# schematics.net
KiCad netlist of a schematic drawn in EAGLE
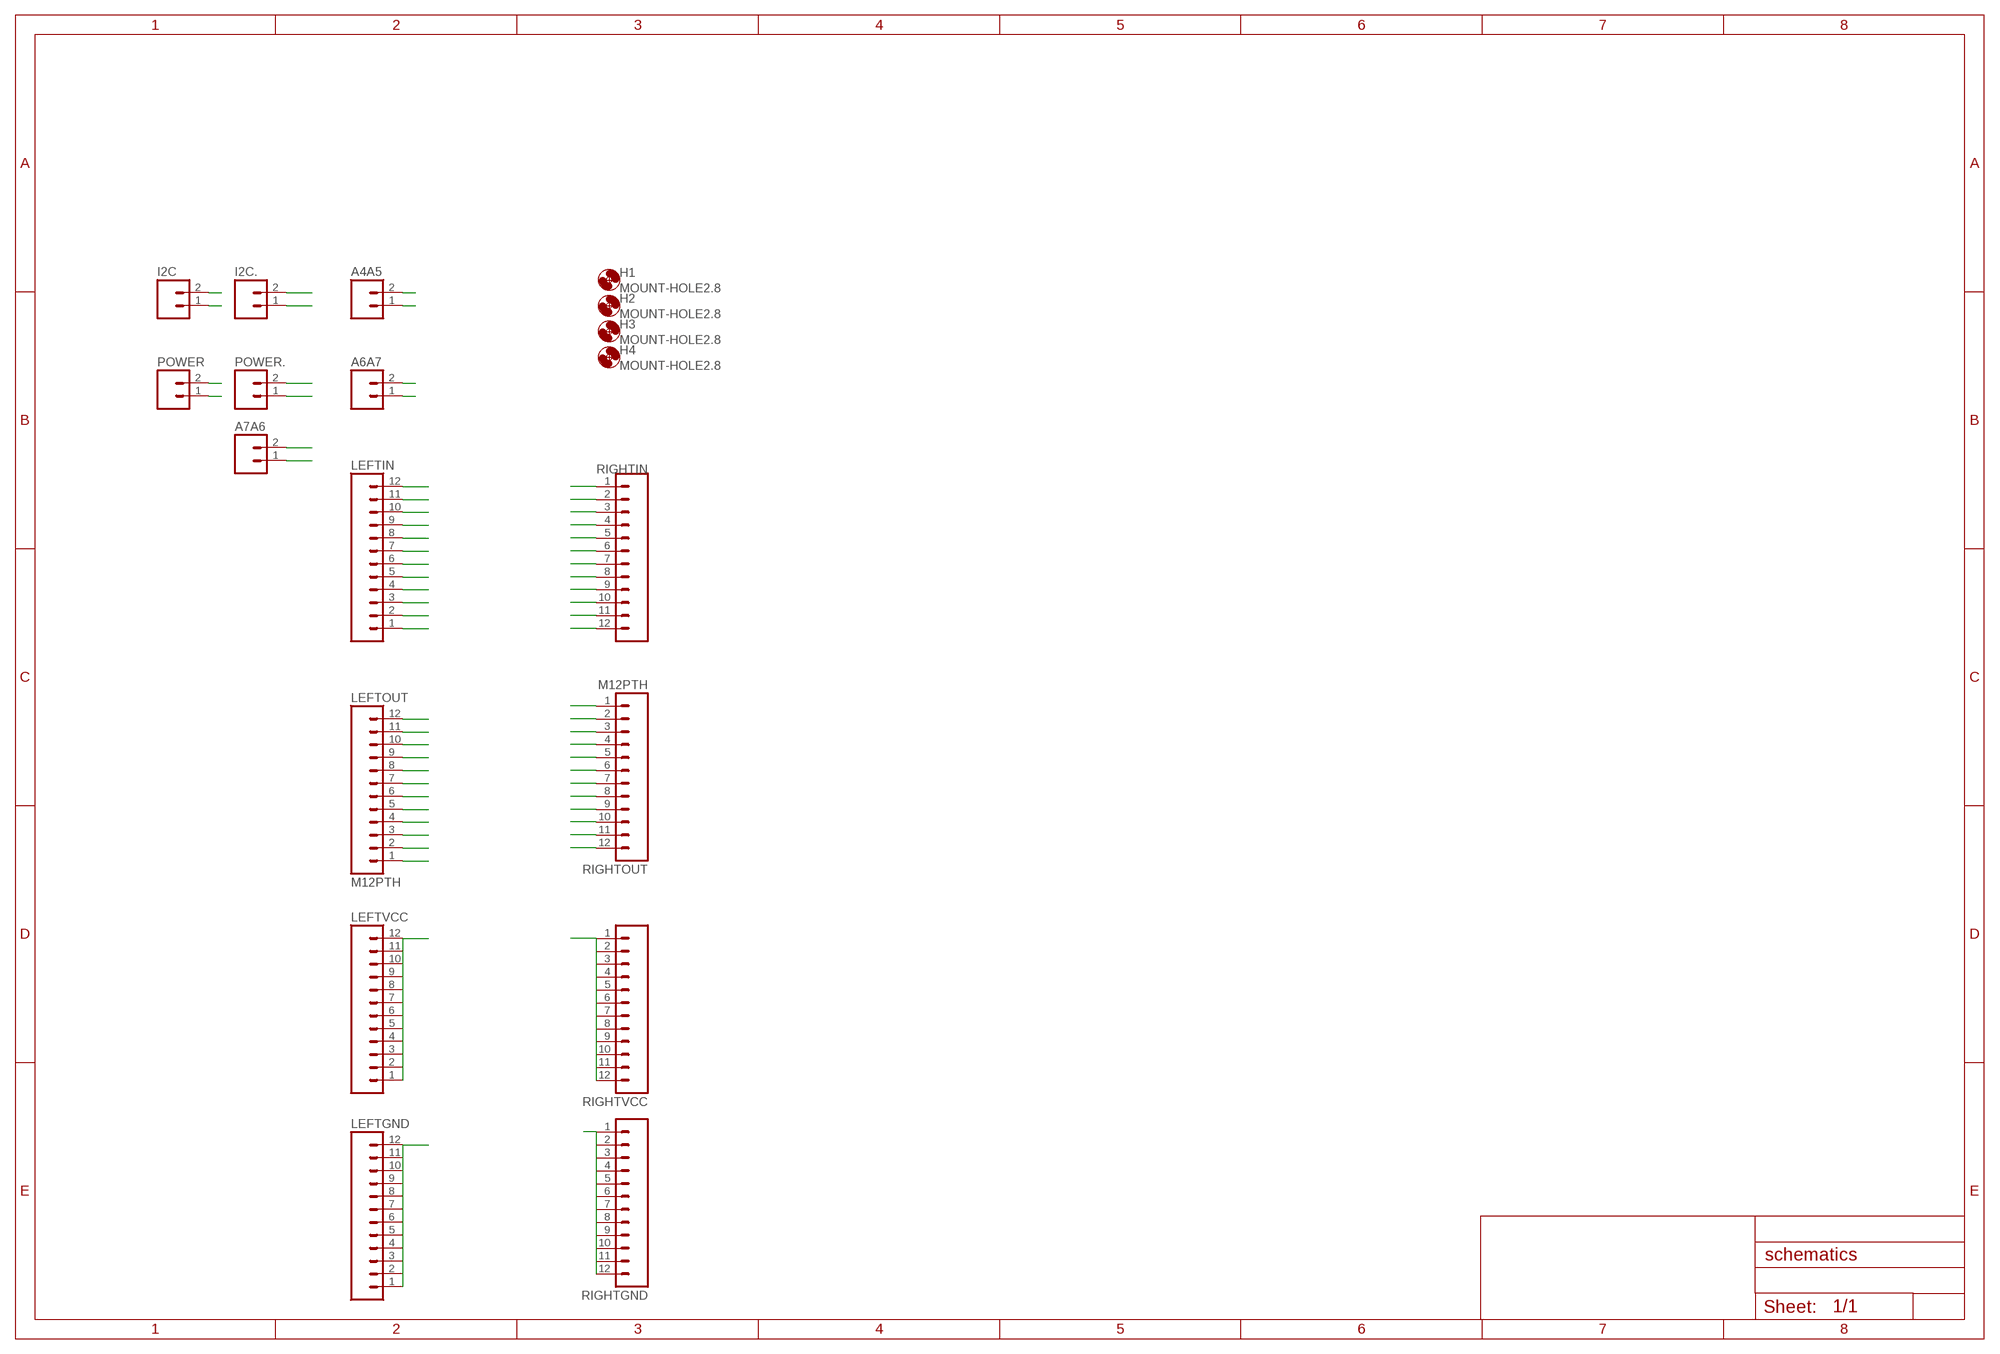
[diagram p0: schematic, sheet 1]

(export (version "E")
  (design (tool "Eeschema 10.0.6"))
  (components
    (comp (ref "A4A5")
      (value "M02PTH")
      (footprint "eagle-import:1X02")
      (libsource (lib "eagle-import") (part "M02PTH"))
    )
    (comp (ref "A6A7")
      (value "M02PTH")
      (footprint "eagle-import:1X02")
      (libsource (lib "eagle-import") (part "M02PTH"))
    )
    (comp (ref "A7A6")
      (value "M02PTH")
      (footprint "eagle-import:1X02")
      (libsource (lib "eagle-import") (part "M02PTH"))
    )
    (comp (ref "H1")
      (value "MOUNT-HOLE2.8")
      (footprint "eagle-import:2,8")
      (libsource (lib "eagle-import") (part "MOUNT-HOLE2.8"))
    )
    (comp (ref "H2")
      (value "MOUNT-HOLE2.8")
      (footprint "eagle-import:2,8")
      (libsource (lib "eagle-import") (part "MOUNT-HOLE2.8"))
    )
    (comp (ref "H3")
      (value "MOUNT-HOLE2.8")
      (footprint "eagle-import:2,8")
      (libsource (lib "eagle-import") (part "MOUNT-HOLE2.8"))
    )
    (comp (ref "H4")
      (value "MOUNT-HOLE2.8")
      (footprint "eagle-import:2,8")
      (libsource (lib "eagle-import") (part "MOUNT-HOLE2.8"))
    )
    (comp (ref "I2C")
      (value "M023.5MM")
      (footprint "eagle-import:SCREWTERMINAL-3.5MM-2")
      (libsource (lib "eagle-import") (part "M023.5MM"))
    )
    (comp (ref "I2C.")
      (value "M02PTH")
      (footprint "eagle-import:1X02")
      (libsource (lib "eagle-import") (part "M02PTH"))
    )
    (comp (ref "LEFTGND")
      (value "M12PTH")
      (footprint "eagle-import:1X12")
      (libsource (lib "eagle-import") (part "M12PTH"))
    )
    (comp (ref "LEFTIN")
      (value "M12PTH")
      (footprint "eagle-import:1X12")
      (libsource (lib "eagle-import") (part "M12PTH"))
    )
    (comp (ref "LEFTOUT")
      (value "M12PTH")
      (footprint "eagle-import:1X12")
      (libsource (lib "eagle-import") (part "M12PTH"))
    )
    (comp (ref "LEFTVCC")
      (value "M12PTH")
      (footprint "eagle-import:1X12")
      (libsource (lib "eagle-import") (part "M12PTH"))
    )
    (comp (ref "POWER")
      (value "M023.5MM")
      (footprint "eagle-import:SCREWTERMINAL-3.5MM-2")
      (libsource (lib "eagle-import") (part "M023.5MM"))
    )
    (comp (ref "POWER.")
      (value "M02PTH")
      (footprint "eagle-import:1X02")
      (libsource (lib "eagle-import") (part "M02PTH"))
    )
    (comp (ref "RIGHTGND")
      (value "M12PTH")
      (footprint "eagle-import:1X12")
      (libsource (lib "eagle-import") (part "M12PTH"))
    )
    (comp (ref "RIGHTIN")
      (value "M12PTH")
      (footprint "eagle-import:1X12")
      (libsource (lib "eagle-import") (part "M12PTH"))
    )
    (comp (ref "RIGHTOUT")
      (value "M12PTH")
      (footprint "eagle-import:1X12")
      (libsource (lib "eagle-import") (part "M12PTH"))
    )
    (comp (ref "RIGHTVCC")
      (value "M12PTH")
      (footprint "eagle-import:1X12")
      (libsource (lib "eagle-import") (part "M12PTH"))
    )
  )
  (nets
    (net (code "1") (name "/2") (class "Default")
      (node (ref "LEFTIN") (pin "8") (pinfunction "8_8") (pintype "passive"))
      (node (ref "LEFTOUT") (pin "8") (pinfunction "8_8") (pintype "passive"))
    )
    (net (code "2") (name "/3") (class "Default")
      (node (ref "LEFTIN") (pin "7") (pinfunction "7_7") (pintype "passive"))
      (node (ref "LEFTOUT") (pin "7") (pinfunction "7_7") (pintype "passive"))
    )
    (net (code "3") (name "/4") (class "Default")
      (node (ref "LEFTIN") (pin "6") (pinfunction "6_6") (pintype "passive"))
      (node (ref "LEFTOUT") (pin "6") (pinfunction "6_6") (pintype "passive"))
    )
    (net (code "4") (name "/5") (class "Default")
      (node (ref "LEFTIN") (pin "5") (pinfunction "5_5") (pintype "passive"))
      (node (ref "LEFTOUT") (pin "5") (pinfunction "5_5") (pintype "passive"))
    )
    (net (code "5") (name "/6") (class "Default")
      (node (ref "LEFTIN") (pin "4") (pinfunction "4_4") (pintype "passive"))
      (node (ref "LEFTOUT") (pin "4") (pinfunction "4_4") (pintype "passive"))
    )
    (net (code "6") (name "/7") (class "Default")
      (node (ref "LEFTIN") (pin "3") (pinfunction "3_3") (pintype "passive"))
      (node (ref "LEFTOUT") (pin "3") (pinfunction "3_3") (pintype "passive"))
    )
    (net (code "7") (name "/8") (class "Default")
      (node (ref "LEFTIN") (pin "2") (pinfunction "2_2") (pintype "passive"))
      (node (ref "LEFTOUT") (pin "2") (pinfunction "2_2") (pintype "passive"))
    )
    (net (code "8") (name "/9") (class "Default")
      (node (ref "LEFTIN") (pin "1") (pinfunction "1_1") (pintype "passive"))
      (node (ref "LEFTOUT") (pin "1") (pinfunction "1_1") (pintype "passive"))
    )
    (net (code "9") (name "/10") (class "Default")
      (node (ref "RIGHTIN") (pin "12") (pinfunction "12_12") (pintype "passive"))
      (node (ref "RIGHTOUT") (pin "1") (pinfunction "1_1") (pintype "passive"))
    )
    (net (code "10") (name "/11") (class "Default")
      (node (ref "RIGHTIN") (pin "11") (pinfunction "11_11") (pintype "passive"))
      (node (ref "RIGHTOUT") (pin "2") (pinfunction "2_2") (pintype "passive"))
    )
    (net (code "11") (name "/12") (class "Default")
      (node (ref "RIGHTIN") (pin "10") (pinfunction "10_10") (pintype "passive"))
      (node (ref "RIGHTOUT") (pin "3") (pinfunction "3_3") (pintype "passive"))
    )
    (net (code "12") (name "/13") (class "Default")
      (node (ref "RIGHTIN") (pin "9") (pinfunction "9_9") (pintype "passive"))
      (node (ref "RIGHTOUT") (pin "4") (pinfunction "4_4") (pintype "passive"))
    )
    (net (code "13") (name "/A0") (class "Default")
      (node (ref "RIGHTIN") (pin "8") (pinfunction "8_8") (pintype "passive"))
      (node (ref "RIGHTOUT") (pin "5") (pinfunction "5_5") (pintype "passive"))
    )
    (net (code "14") (name "/A1") (class "Default")
      (node (ref "RIGHTIN") (pin "7") (pinfunction "7_7") (pintype "passive"))
      (node (ref "RIGHTOUT") (pin "6") (pinfunction "6_6") (pintype "passive"))
    )
    (net (code "15") (name "/A2") (class "Default")
      (node (ref "RIGHTIN") (pin "6") (pinfunction "6_6") (pintype "passive"))
      (node (ref "RIGHTOUT") (pin "7") (pinfunction "7_7") (pintype "passive"))
    )
    (net (code "16") (name "/A3") (class "Default")
      (node (ref "RIGHTIN") (pin "5") (pinfunction "5_5") (pintype "passive"))
      (node (ref "RIGHTOUT") (pin "8") (pinfunction "8_8") (pintype "passive"))
    )
    (net (code "17") (name "/A4SDA") (class "Default")
      (node (ref "A4A5") (pin "1") (pinfunction "1_1") (pintype "passive"))
      (node (ref "I2C") (pin "1") (pinfunction "1_1") (pintype "passive"))
      (node (ref "I2C.") (pin "1") (pinfunction "1_1") (pintype "passive"))
    )
    (net (code "18") (name "/A5SCL") (class "Default")
      (node (ref "A4A5") (pin "2") (pinfunction "2_2") (pintype "passive"))
      (node (ref "I2C") (pin "2") (pinfunction "2_2") (pintype "passive"))
      (node (ref "I2C.") (pin "2") (pinfunction "2_2") (pintype "passive"))
    )
    (net (code "19") (name "/A6") (class "Default")
      (node (ref "A6A7") (pin "1") (pinfunction "1_1") (pintype "passive"))
      (node (ref "A7A6") (pin "1") (pinfunction "1_1") (pintype "passive"))
    )
    (net (code "20") (name "/A7") (class "Default")
      (node (ref "A6A7") (pin "2") (pinfunction "2_2") (pintype "passive"))
      (node (ref "A7A6") (pin "2") (pinfunction "2_2") (pintype "passive"))
    )
    (net (code "21") (name "/GND") (class "Default")
      (node (ref "LEFTGND") (pin "1") (pinfunction "1_1") (pintype "passive"))
      (node (ref "LEFTGND") (pin "10") (pinfunction "10_10") (pintype "passive"))
      (node (ref "LEFTGND") (pin "11") (pinfunction "11_11") (pintype "passive"))
      (node (ref "LEFTGND") (pin "12") (pinfunction "12_12") (pintype "passive"))
      (node (ref "LEFTGND") (pin "2") (pinfunction "2_2") (pintype "passive"))
      (node (ref "LEFTGND") (pin "3") (pinfunction "3_3") (pintype "passive"))
      (node (ref "LEFTGND") (pin "4") (pinfunction "4_4") (pintype "passive"))
      (node (ref "LEFTGND") (pin "5") (pinfunction "5_5") (pintype "passive"))
      (node (ref "LEFTGND") (pin "6") (pinfunction "6_6") (pintype "passive"))
      (node (ref "LEFTGND") (pin "7") (pinfunction "7_7") (pintype "passive"))
      (node (ref "LEFTGND") (pin "8") (pinfunction "8_8") (pintype "passive"))
      (node (ref "LEFTGND") (pin "9") (pinfunction "9_9") (pintype "passive"))
      (node (ref "LEFTIN") (pin "9") (pinfunction "9_9") (pintype "passive"))
      (node (ref "LEFTOUT") (pin "9") (pinfunction "9_9") (pintype "passive"))
      (node (ref "POWER") (pin "1") (pinfunction "1_1") (pintype "passive"))
      (node (ref "POWER.") (pin "1") (pinfunction "1_1") (pintype "passive"))
      (node (ref "RIGHTGND") (pin "1") (pinfunction "1_1") (pintype "passive"))
      (node (ref "RIGHTGND") (pin "10") (pinfunction "10_10") (pintype "passive"))
      (node (ref "RIGHTGND") (pin "11") (pinfunction "11_11") (pintype "passive"))
      (node (ref "RIGHTGND") (pin "12") (pinfunction "12_12") (pintype "passive"))
      (node (ref "RIGHTGND") (pin "2") (pinfunction "2_2") (pintype "passive"))
      (node (ref "RIGHTGND") (pin "3") (pinfunction "3_3") (pintype "passive"))
      (node (ref "RIGHTGND") (pin "4") (pinfunction "4_4") (pintype "passive"))
      (node (ref "RIGHTGND") (pin "5") (pinfunction "5_5") (pintype "passive"))
      (node (ref "RIGHTGND") (pin "6") (pinfunction "6_6") (pintype "passive"))
      (node (ref "RIGHTGND") (pin "7") (pinfunction "7_7") (pintype "passive"))
      (node (ref "RIGHTGND") (pin "8") (pinfunction "8_8") (pintype "passive"))
      (node (ref "RIGHTGND") (pin "9") (pinfunction "9_9") (pintype "passive"))
      (node (ref "RIGHTIN") (pin "2") (pinfunction "2_2") (pintype "passive"))
      (node (ref "RIGHTOUT") (pin "11") (pinfunction "11_11") (pintype "passive"))
    )
    (net (code "22") (name "/RST") (class "Default")
      (node (ref "LEFTIN") (pin "10") (pinfunction "10_10") (pintype "passive"))
      (node (ref "LEFTOUT") (pin "10") (pinfunction "10_10") (pintype "passive"))
      (node (ref "RIGHTIN") (pin "3") (pinfunction "3_3") (pintype "passive"))
      (node (ref "RIGHTOUT") (pin "10") (pinfunction "10_10") (pintype "passive"))
    )
    (net (code "23") (name "/RX") (class "Default")
      (node (ref "LEFTIN") (pin "11") (pinfunction "11_11") (pintype "passive"))
      (node (ref "LEFTOUT") (pin "11") (pinfunction "11_11") (pintype "passive"))
    )
    (net (code "24") (name "/TX") (class "Default")
      (node (ref "LEFTIN") (pin "12") (pinfunction "12_12") (pintype "passive"))
      (node (ref "LEFTOUT") (pin "12") (pinfunction "12_12") (pintype "passive"))
    )
    (net (code "25") (name "/VCC") (class "Default")
      (node (ref "LEFTVCC") (pin "1") (pinfunction "1_1") (pintype "passive"))
      (node (ref "LEFTVCC") (pin "10") (pinfunction "10_10") (pintype "passive"))
      (node (ref "LEFTVCC") (pin "11") (pinfunction "11_11") (pintype "passive"))
      (node (ref "LEFTVCC") (pin "12") (pinfunction "12_12") (pintype "passive"))
      (node (ref "LEFTVCC") (pin "2") (pinfunction "2_2") (pintype "passive"))
      (node (ref "LEFTVCC") (pin "3") (pinfunction "3_3") (pintype "passive"))
      (node (ref "LEFTVCC") (pin "4") (pinfunction "4_4") (pintype "passive"))
      (node (ref "LEFTVCC") (pin "5") (pinfunction "5_5") (pintype "passive"))
      (node (ref "LEFTVCC") (pin "6") (pinfunction "6_6") (pintype "passive"))
      (node (ref "LEFTVCC") (pin "7") (pinfunction "7_7") (pintype "passive"))
      (node (ref "LEFTVCC") (pin "8") (pinfunction "8_8") (pintype "passive"))
      (node (ref "LEFTVCC") (pin "9") (pinfunction "9_9") (pintype "passive"))
      (node (ref "RIGHTIN") (pin "4") (pinfunction "4_4") (pintype "passive"))
      (node (ref "RIGHTOUT") (pin "9") (pinfunction "9_9") (pintype "passive"))
      (node (ref "RIGHTVCC") (pin "1") (pinfunction "1_1") (pintype "passive"))
      (node (ref "RIGHTVCC") (pin "10") (pinfunction "10_10") (pintype "passive"))
      (node (ref "RIGHTVCC") (pin "11") (pinfunction "11_11") (pintype "passive"))
      (node (ref "RIGHTVCC") (pin "12") (pinfunction "12_12") (pintype "passive"))
      (node (ref "RIGHTVCC") (pin "2") (pinfunction "2_2") (pintype "passive"))
      (node (ref "RIGHTVCC") (pin "3") (pinfunction "3_3") (pintype "passive"))
      (node (ref "RIGHTVCC") (pin "4") (pinfunction "4_4") (pintype "passive"))
      (node (ref "RIGHTVCC") (pin "5") (pinfunction "5_5") (pintype "passive"))
      (node (ref "RIGHTVCC") (pin "6") (pinfunction "6_6") (pintype "passive"))
      (node (ref "RIGHTVCC") (pin "7") (pinfunction "7_7") (pintype "passive"))
      (node (ref "RIGHTVCC") (pin "8") (pinfunction "8_8") (pintype "passive"))
      (node (ref "RIGHTVCC") (pin "9") (pinfunction "9_9") (pintype "passive"))
    )
    (net (code "26") (name "/VIN") (class "Default")
      (node (ref "POWER") (pin "2") (pinfunction "2_2") (pintype "passive"))
      (node (ref "POWER.") (pin "2") (pinfunction "2_2") (pintype "passive"))
      (node (ref "RIGHTIN") (pin "1") (pinfunction "1_1") (pintype "passive"))
    )
    (net (code "27") (name "unconnected-(RIGHTOUT-Pad12)") (class "Default")
      (node (ref "RIGHTOUT") (pin "12") (pinfunction "12_12") (pintype "passive"))
    )
  )
)
